# flex_led_wrap.net
KiCad netlist of a schematic drawn in EAGLE
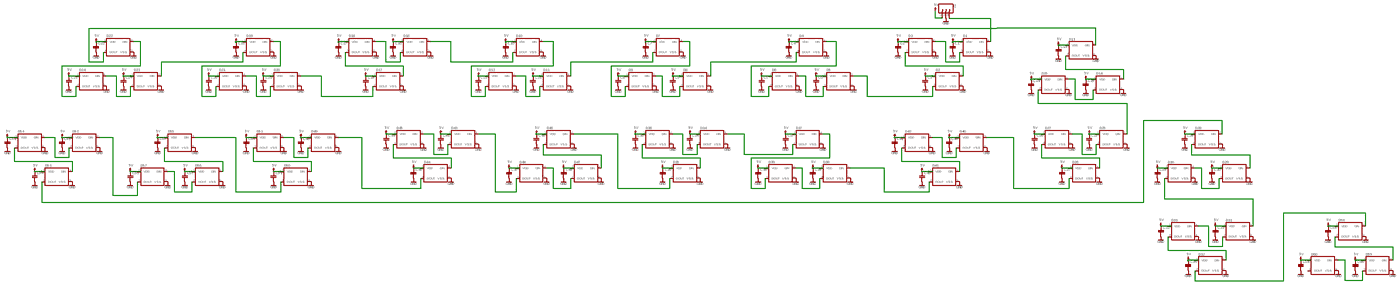
[diagram p0: schematic, sheet 1, overview]
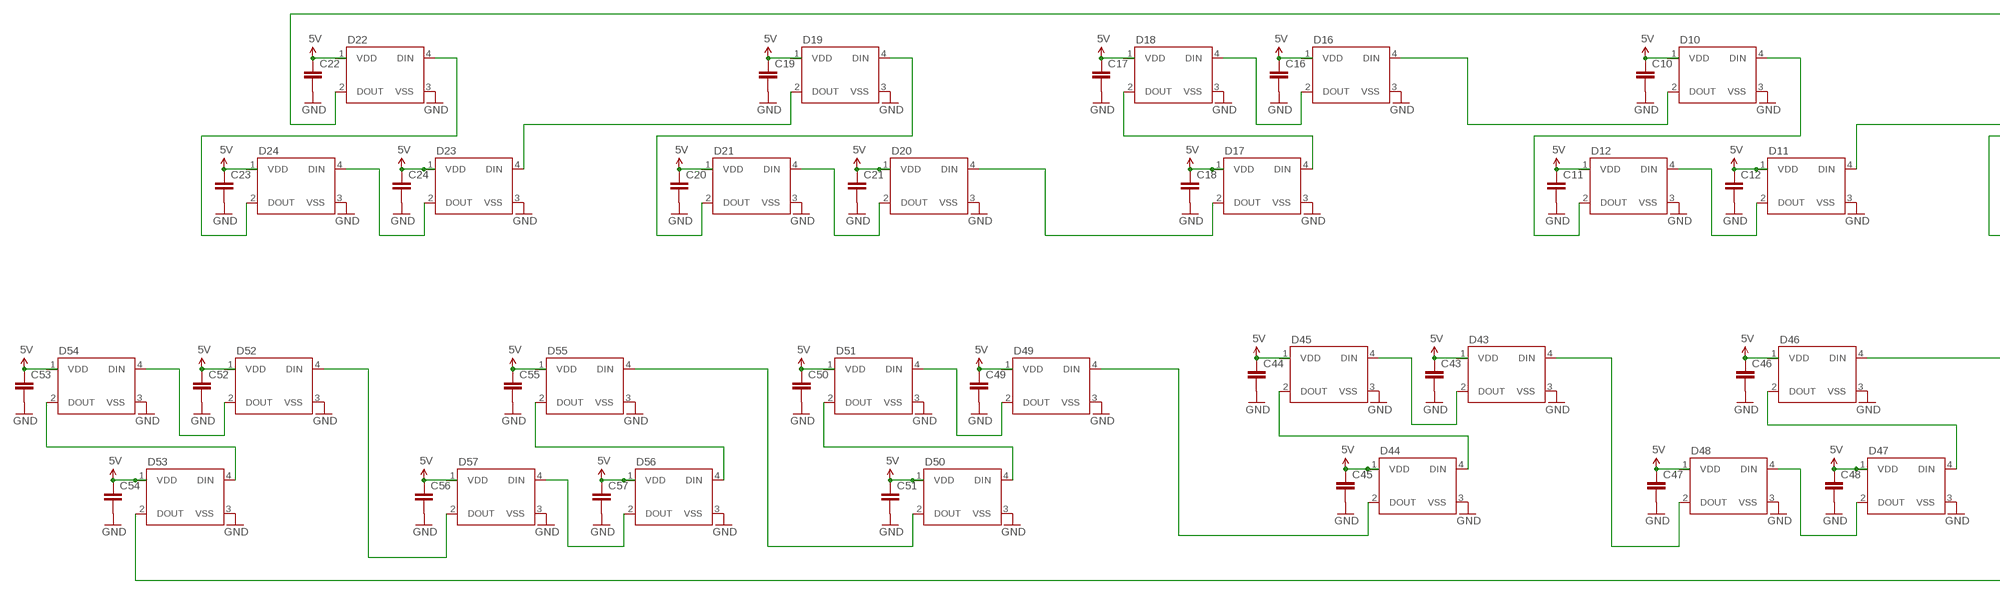
[diagram p1: schematic, sheet 1, part 1 of 4]
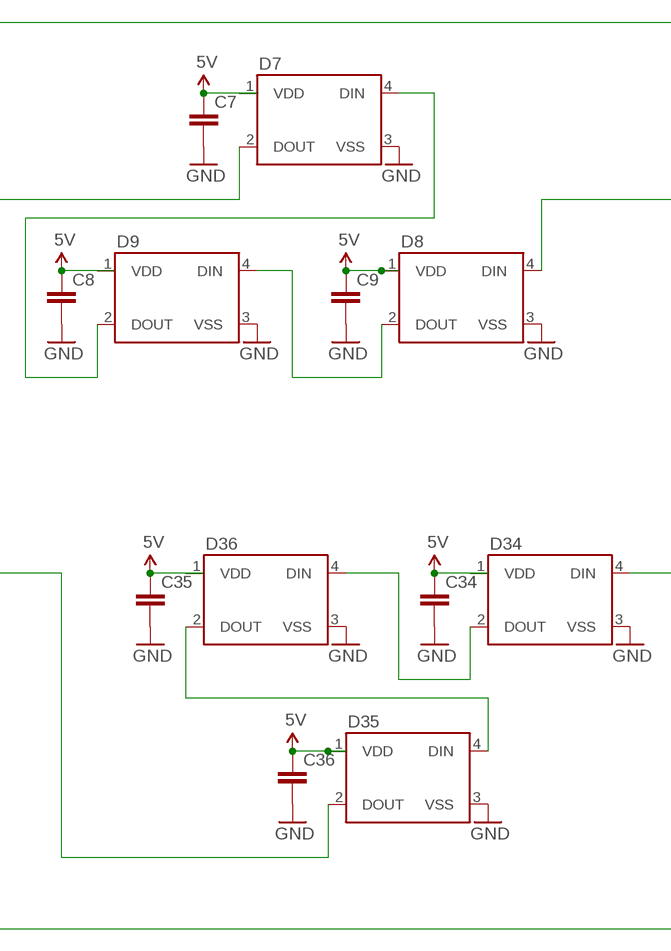
[diagram p2: schematic, sheet 1, part 2 of 4]
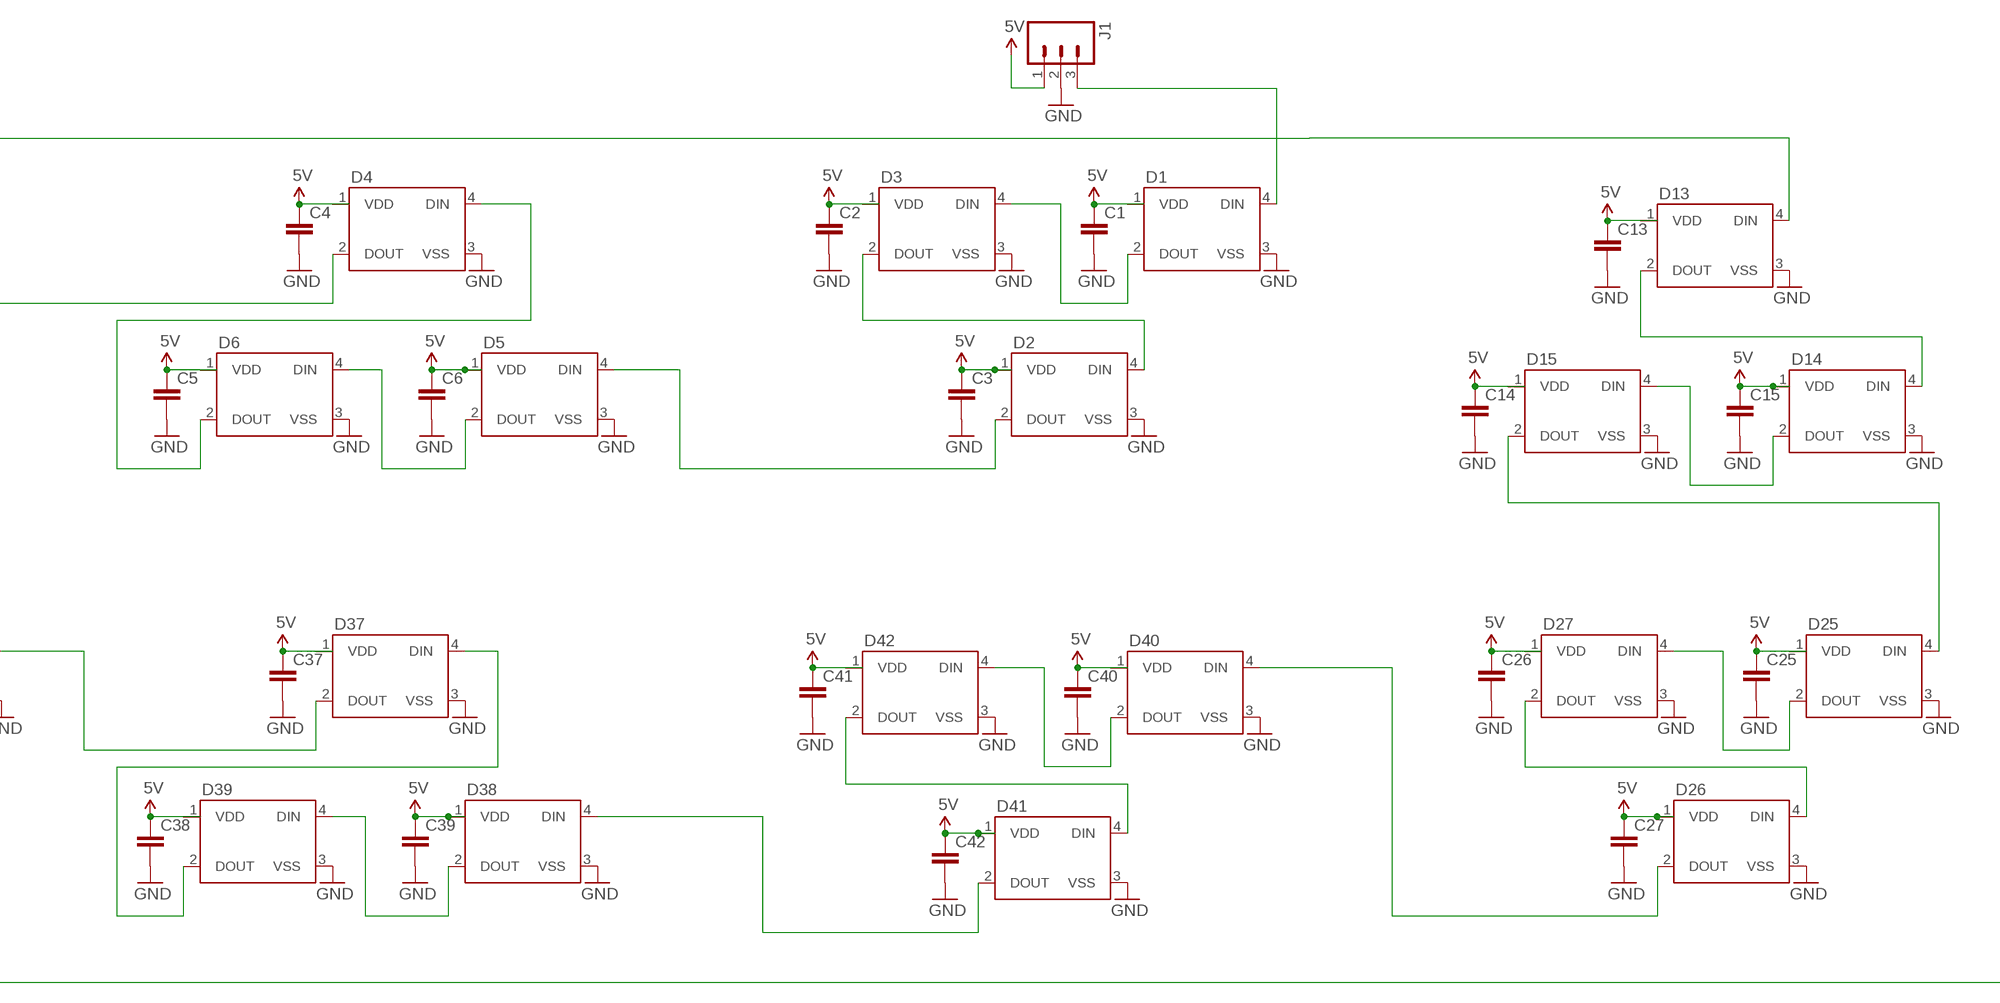
[diagram p3: schematic, sheet 1, part 3 of 4]
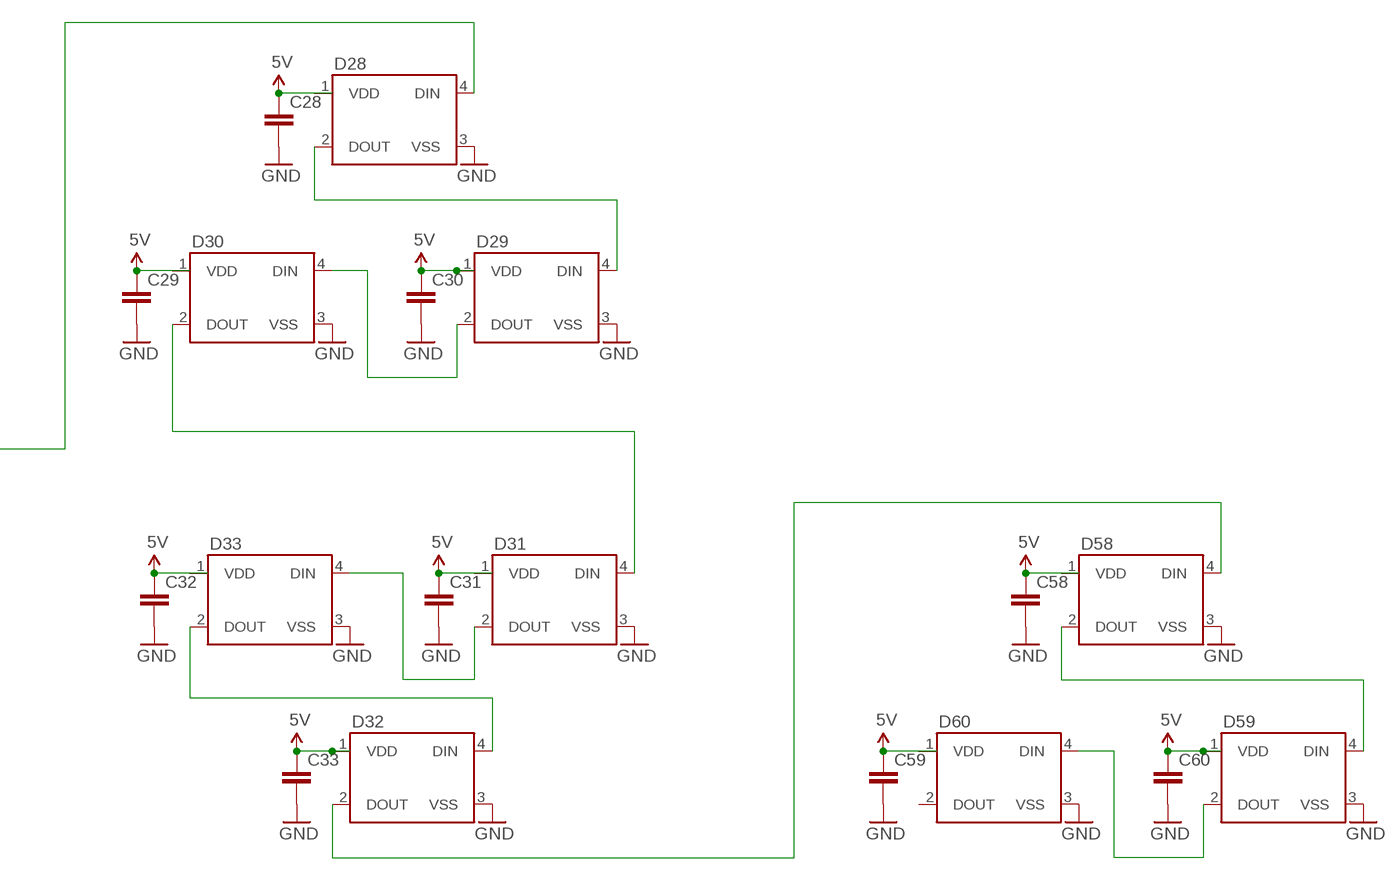
[diagram p4: schematic, sheet 1, part 4 of 4]

(export (version "E")
  (design (tool "Eeschema 10.0.6"))
  (components
    (comp (ref "C1")
      (value "CAP0805")
      (footprint "eagle-import:0805")
      (libsource (lib "eagle-import") (part "CAP0805"))
    )
    (comp (ref "C2")
      (value "CAP0805")
      (footprint "eagle-import:0805")
      (libsource (lib "eagle-import") (part "CAP0805"))
    )
    (comp (ref "C3")
      (value "CAP0805")
      (footprint "eagle-import:0805")
      (libsource (lib "eagle-import") (part "CAP0805"))
    )
    (comp (ref "C4")
      (value "CAP0805")
      (footprint "eagle-import:0805")
      (libsource (lib "eagle-import") (part "CAP0805"))
    )
    (comp (ref "C5")
      (value "CAP0805")
      (footprint "eagle-import:0805")
      (libsource (lib "eagle-import") (part "CAP0805"))
    )
    (comp (ref "C6")
      (value "CAP0805")
      (footprint "eagle-import:0805")
      (libsource (lib "eagle-import") (part "CAP0805"))
    )
    (comp (ref "C7")
      (value "CAP0805")
      (footprint "eagle-import:0805")
      (libsource (lib "eagle-import") (part "CAP0805"))
    )
    (comp (ref "C8")
      (value "CAP0805")
      (footprint "eagle-import:0805")
      (libsource (lib "eagle-import") (part "CAP0805"))
    )
    (comp (ref "C9")
      (value "CAP0805")
      (footprint "eagle-import:0805")
      (libsource (lib "eagle-import") (part "CAP0805"))
    )
    (comp (ref "C10")
      (value "CAP0805")
      (footprint "eagle-import:0805")
      (libsource (lib "eagle-import") (part "CAP0805"))
    )
    (comp (ref "C11")
      (value "CAP0805")
      (footprint "eagle-import:0805")
      (libsource (lib "eagle-import") (part "CAP0805"))
    )
    (comp (ref "C12")
      (value "CAP0805")
      (footprint "eagle-import:0805")
      (libsource (lib "eagle-import") (part "CAP0805"))
    )
    (comp (ref "C13")
      (value "CAP0805")
      (footprint "eagle-import:0805")
      (libsource (lib "eagle-import") (part "CAP0805"))
    )
    (comp (ref "C14")
      (value "CAP0805")
      (footprint "eagle-import:0805")
      (libsource (lib "eagle-import") (part "CAP0805"))
    )
    (comp (ref "C15")
      (value "CAP0805")
      (footprint "eagle-import:0805")
      (libsource (lib "eagle-import") (part "CAP0805"))
    )
    (comp (ref "C16")
      (value "CAP0805")
      (footprint "eagle-import:0805")
      (libsource (lib "eagle-import") (part "CAP0805"))
    )
    (comp (ref "C17")
      (value "CAP0805")
      (footprint "eagle-import:0805")
      (libsource (lib "eagle-import") (part "CAP0805"))
    )
    (comp (ref "C18")
      (value "CAP0805")
      (footprint "eagle-import:0805")
      (libsource (lib "eagle-import") (part "CAP0805"))
    )
    (comp (ref "C19")
      (value "CAP0805")
      (footprint "eagle-import:0805")
      (libsource (lib "eagle-import") (part "CAP0805"))
    )
    (comp (ref "C20")
      (value "CAP0805")
      (footprint "eagle-import:0805")
      (libsource (lib "eagle-import") (part "CAP0805"))
    )
    (comp (ref "C21")
      (value "CAP0805")
      (footprint "eagle-import:0805")
      (libsource (lib "eagle-import") (part "CAP0805"))
    )
    (comp (ref "C22")
      (value "CAP0805")
      (footprint "eagle-import:0805")
      (libsource (lib "eagle-import") (part "CAP0805"))
    )
    (comp (ref "C23")
      (value "CAP0805")
      (footprint "eagle-import:0805")
      (libsource (lib "eagle-import") (part "CAP0805"))
    )
    (comp (ref "C24")
      (value "CAP0805")
      (footprint "eagle-import:0805")
      (libsource (lib "eagle-import") (part "CAP0805"))
    )
    (comp (ref "C25")
      (value "CAP0805")
      (footprint "eagle-import:0805")
      (libsource (lib "eagle-import") (part "CAP0805"))
    )
    (comp (ref "C26")
      (value "CAP0805")
      (footprint "eagle-import:0805")
      (libsource (lib "eagle-import") (part "CAP0805"))
    )
    (comp (ref "C27")
      (value "CAP0805")
      (footprint "eagle-import:0805")
      (libsource (lib "eagle-import") (part "CAP0805"))
    )
    (comp (ref "C28")
      (value "CAP0805")
      (footprint "eagle-import:0805")
      (libsource (lib "eagle-import") (part "CAP0805"))
    )
    (comp (ref "C29")
      (value "CAP0805")
      (footprint "eagle-import:0805")
      (libsource (lib "eagle-import") (part "CAP0805"))
    )
    (comp (ref "C30")
      (value "CAP0805")
      (footprint "eagle-import:0805")
      (libsource (lib "eagle-import") (part "CAP0805"))
    )
    (comp (ref "C31")
      (value "CAP0805")
      (footprint "eagle-import:0805")
      (libsource (lib "eagle-import") (part "CAP0805"))
    )
    (comp (ref "C32")
      (value "CAP0805")
      (footprint "eagle-import:0805")
      (libsource (lib "eagle-import") (part "CAP0805"))
    )
    (comp (ref "C33")
      (value "CAP0805")
      (footprint "eagle-import:0805")
      (libsource (lib "eagle-import") (part "CAP0805"))
    )
    (comp (ref "C34")
      (value "CAP0805")
      (footprint "eagle-import:0805")
      (libsource (lib "eagle-import") (part "CAP0805"))
    )
    (comp (ref "C35")
      (value "CAP0805")
      (footprint "eagle-import:0805")
      (libsource (lib "eagle-import") (part "CAP0805"))
    )
    (comp (ref "C36")
      (value "CAP0805")
      (footprint "eagle-import:0805")
      (libsource (lib "eagle-import") (part "CAP0805"))
    )
    (comp (ref "C37")
      (value "CAP0805")
      (footprint "eagle-import:0805")
      (libsource (lib "eagle-import") (part "CAP0805"))
    )
    (comp (ref "C38")
      (value "CAP0805")
      (footprint "eagle-import:0805")
      (libsource (lib "eagle-import") (part "CAP0805"))
    )
    (comp (ref "C39")
      (value "CAP0805")
      (footprint "eagle-import:0805")
      (libsource (lib "eagle-import") (part "CAP0805"))
    )
    (comp (ref "C40")
      (value "CAP0805")
      (footprint "eagle-import:0805")
      (libsource (lib "eagle-import") (part "CAP0805"))
    )
    (comp (ref "C41")
      (value "CAP0805")
      (footprint "eagle-import:0805")
      (libsource (lib "eagle-import") (part "CAP0805"))
    )
    (comp (ref "C42")
      (value "CAP0805")
      (footprint "eagle-import:0805")
      (libsource (lib "eagle-import") (part "CAP0805"))
    )
    (comp (ref "C43")
      (value "CAP0805")
      (footprint "eagle-import:0805")
      (libsource (lib "eagle-import") (part "CAP0805"))
    )
    (comp (ref "C44")
      (value "CAP0805")
      (footprint "eagle-import:0805")
      (libsource (lib "eagle-import") (part "CAP0805"))
    )
    (comp (ref "C45")
      (value "CAP0805")
      (footprint "eagle-import:0805")
      (libsource (lib "eagle-import") (part "CAP0805"))
    )
    (comp (ref "C46")
      (value "CAP0805")
      (footprint "eagle-import:0805")
      (libsource (lib "eagle-import") (part "CAP0805"))
    )
    (comp (ref "C47")
      (value "CAP0805")
      (footprint "eagle-import:0805")
      (libsource (lib "eagle-import") (part "CAP0805"))
    )
    (comp (ref "C48")
      (value "CAP0805")
      (footprint "eagle-import:0805")
      (libsource (lib "eagle-import") (part "CAP0805"))
    )
    (comp (ref "C49")
      (value "CAP0805")
      (footprint "eagle-import:0805")
      (libsource (lib "eagle-import") (part "CAP0805"))
    )
    (comp (ref "C50")
      (value "CAP0805")
      (footprint "eagle-import:0805")
      (libsource (lib "eagle-import") (part "CAP0805"))
    )
    (comp (ref "C51")
      (value "CAP0805")
      (footprint "eagle-import:0805")
      (libsource (lib "eagle-import") (part "CAP0805"))
    )
    (comp (ref "C52")
      (value "CAP0805")
      (footprint "eagle-import:0805")
      (libsource (lib "eagle-import") (part "CAP0805"))
    )
    (comp (ref "C53")
      (value "CAP0805")
      (footprint "eagle-import:0805")
      (libsource (lib "eagle-import") (part "CAP0805"))
    )
    (comp (ref "C54")
      (value "CAP0805")
      (footprint "eagle-import:0805")
      (libsource (lib "eagle-import") (part "CAP0805"))
    )
    (comp (ref "C55")
      (value "CAP0805")
      (footprint "eagle-import:0805")
      (libsource (lib "eagle-import") (part "CAP0805"))
    )
    (comp (ref "C56")
      (value "CAP0805")
      (footprint "eagle-import:0805")
      (libsource (lib "eagle-import") (part "CAP0805"))
    )
    (comp (ref "C57")
      (value "CAP0805")
      (footprint "eagle-import:0805")
      (libsource (lib "eagle-import") (part "CAP0805"))
    )
    (comp (ref "C58")
      (value "CAP0805")
      (footprint "eagle-import:0805")
      (libsource (lib "eagle-import") (part "CAP0805"))
    )
    (comp (ref "C59")
      (value "CAP0805")
      (footprint "eagle-import:0805")
      (libsource (lib "eagle-import") (part "CAP0805"))
    )
    (comp (ref "C60")
      (value "CAP0805")
      (footprint "eagle-import:0805")
      (libsource (lib "eagle-import") (part "CAP0805"))
    )
    (comp (ref "D1")
      (value "WS2812B")
      (footprint "eagle-import:WS2812B")
      (libsource (lib "eagle-import") (part "WS2812B"))
    )
    (comp (ref "D2")
      (value "WS2812B")
      (footprint "eagle-import:WS2812B")
      (libsource (lib "eagle-import") (part "WS2812B"))
    )
    (comp (ref "D3")
      (value "WS2812B")
      (footprint "eagle-import:WS2812B")
      (libsource (lib "eagle-import") (part "WS2812B"))
    )
    (comp (ref "D4")
      (value "WS2812B")
      (footprint "eagle-import:WS2812B")
      (libsource (lib "eagle-import") (part "WS2812B"))
    )
    (comp (ref "D5")
      (value "WS2812B")
      (footprint "eagle-import:WS2812B")
      (libsource (lib "eagle-import") (part "WS2812B"))
    )
    (comp (ref "D6")
      (value "WS2812B")
      (footprint "eagle-import:WS2812B")
      (libsource (lib "eagle-import") (part "WS2812B"))
    )
    (comp (ref "D7")
      (value "WS2812B")
      (footprint "eagle-import:WS2812B")
      (libsource (lib "eagle-import") (part "WS2812B"))
    )
    (comp (ref "D8")
      (value "WS2812B")
      (footprint "eagle-import:WS2812B")
      (libsource (lib "eagle-import") (part "WS2812B"))
    )
    (comp (ref "D9")
      (value "WS2812B")
      (footprint "eagle-import:WS2812B")
      (libsource (lib "eagle-import") (part "WS2812B"))
    )
    (comp (ref "D10")
      (value "WS2812B")
      (footprint "eagle-import:WS2812B")
      (libsource (lib "eagle-import") (part "WS2812B"))
    )
    (comp (ref "D11")
      (value "WS2812B")
      (footprint "eagle-import:WS2812B")
      (libsource (lib "eagle-import") (part "WS2812B"))
    )
    (comp (ref "D12")
      (value "WS2812B")
      (footprint "eagle-import:WS2812B")
      (libsource (lib "eagle-import") (part "WS2812B"))
    )
    (comp (ref "D13")
      (value "WS2812B")
      (footprint "eagle-import:WS2812B")
      (libsource (lib "eagle-import") (part "WS2812B"))
    )
    (comp (ref "D14")
      (value "WS2812B")
      (footprint "eagle-import:WS2812B")
      (libsource (lib "eagle-import") (part "WS2812B"))
    )
    (comp (ref "D15")
      (value "WS2812B")
      (footprint "eagle-import:WS2812B")
      (libsource (lib "eagle-import") (part "WS2812B"))
    )
    (comp (ref "D16")
      (value "WS2812B")
      (footprint "eagle-import:WS2812B")
      (libsource (lib "eagle-import") (part "WS2812B"))
    )
    (comp (ref "D17")
      (value "WS2812B")
      (footprint "eagle-import:WS2812B")
      (libsource (lib "eagle-import") (part "WS2812B"))
    )
    (comp (ref "D18")
      (value "WS2812B")
      (footprint "eagle-import:WS2812B")
      (libsource (lib "eagle-import") (part "WS2812B"))
    )
    (comp (ref "D19")
      (value "WS2812B")
      (footprint "eagle-import:WS2812B")
      (libsource (lib "eagle-import") (part "WS2812B"))
    )
    (comp (ref "D20")
      (value "WS2812B")
      (footprint "eagle-import:WS2812B")
      (libsource (lib "eagle-import") (part "WS2812B"))
    )
    (comp (ref "D21")
      (value "WS2812B")
      (footprint "eagle-import:WS2812B")
      (libsource (lib "eagle-import") (part "WS2812B"))
    )
    (comp (ref "D22")
      (value "WS2812B")
      (footprint "eagle-import:WS2812B")
      (libsource (lib "eagle-import") (part "WS2812B"))
    )
    (comp (ref "D23")
      (value "WS2812B")
      (footprint "eagle-import:WS2812B")
      (libsource (lib "eagle-import") (part "WS2812B"))
    )
    (comp (ref "D24")
      (value "WS2812B")
      (footprint "eagle-import:WS2812B")
      (libsource (lib "eagle-import") (part "WS2812B"))
    )
    (comp (ref "D25")
      (value "WS2812B")
      (footprint "eagle-import:WS2812B")
      (libsource (lib "eagle-import") (part "WS2812B"))
    )
    (comp (ref "D26")
      (value "WS2812B")
      (footprint "eagle-import:WS2812B")
      (libsource (lib "eagle-import") (part "WS2812B"))
    )
    (comp (ref "D27")
      (value "WS2812B")
      (footprint "eagle-import:WS2812B")
      (libsource (lib "eagle-import") (part "WS2812B"))
    )
    (comp (ref "D28")
      (value "WS2812B")
      (footprint "eagle-import:WS2812B")
      (libsource (lib "eagle-import") (part "WS2812B"))
    )
    (comp (ref "D29")
      (value "WS2812B")
      (footprint "eagle-import:WS2812B")
      (libsource (lib "eagle-import") (part "WS2812B"))
    )
    (comp (ref "D30")
      (value "WS2812B")
      (footprint "eagle-import:WS2812B")
      (libsource (lib "eagle-import") (part "WS2812B"))
    )
    (comp (ref "D31")
      (value "WS2812B")
      (footprint "eagle-import:WS2812B")
      (libsource (lib "eagle-import") (part "WS2812B"))
    )
    (comp (ref "D32")
      (value "WS2812B")
      (footprint "eagle-import:WS2812B")
      (libsource (lib "eagle-import") (part "WS2812B"))
    )
    (comp (ref "D33")
      (value "WS2812B")
      (footprint "eagle-import:WS2812B")
      (libsource (lib "eagle-import") (part "WS2812B"))
    )
    (comp (ref "D34")
      (value "WS2812B")
      (footprint "eagle-import:WS2812B")
      (libsource (lib "eagle-import") (part "WS2812B"))
    )
    (comp (ref "D35")
      (value "WS2812B")
      (footprint "eagle-import:WS2812B")
      (libsource (lib "eagle-import") (part "WS2812B"))
    )
    (comp (ref "D36")
      (value "WS2812B")
      (footprint "eagle-import:WS2812B")
      (libsource (lib "eagle-import") (part "WS2812B"))
    )
    (comp (ref "D37")
      (value "WS2812B")
      (footprint "eagle-import:WS2812B")
      (libsource (lib "eagle-import") (part "WS2812B"))
    )
    (comp (ref "D38")
      (value "WS2812B")
      (footprint "eagle-import:WS2812B")
      (libsource (lib "eagle-import") (part "WS2812B"))
    )
    (comp (ref "D39")
      (value "WS2812B")
      (footprint "eagle-import:WS2812B")
      (libsource (lib "eagle-import") (part "WS2812B"))
    )
    (comp (ref "D40")
      (value "WS2812B")
      (footprint "eagle-import:WS2812B")
      (libsource (lib "eagle-import") (part "WS2812B"))
    )
    (comp (ref "D41")
      (value "WS2812B")
      (footprint "eagle-import:WS2812B")
      (libsource (lib "eagle-import") (part "WS2812B"))
    )
    (comp (ref "D42")
      (value "WS2812B")
      (footprint "eagle-import:WS2812B")
      (libsource (lib "eagle-import") (part "WS2812B"))
    )
    (comp (ref "D43")
      (value "WS2812B")
      (footprint "eagle-import:WS2812B")
      (libsource (lib "eagle-import") (part "WS2812B"))
    )
    (comp (ref "D44")
      (value "WS2812B")
      (footprint "eagle-import:WS2812B")
      (libsource (lib "eagle-import") (part "WS2812B"))
    )
    (comp (ref "D45")
      (value "WS2812B")
      (footprint "eagle-import:WS2812B")
      (libsource (lib "eagle-import") (part "WS2812B"))
    )
    (comp (ref "D46")
      (value "WS2812B")
      (footprint "eagle-import:WS2812B")
      (libsource (lib "eagle-import") (part "WS2812B"))
    )
    (comp (ref "D47")
      (value "WS2812B")
      (footprint "eagle-import:WS2812B")
      (libsource (lib "eagle-import") (part "WS2812B"))
    )
    (comp (ref "D48")
      (value "WS2812B")
      (footprint "eagle-import:WS2812B")
      (libsource (lib "eagle-import") (part "WS2812B"))
    )
    (comp (ref "D49")
      (value "WS2812B")
      (footprint "eagle-import:WS2812B")
      (libsource (lib "eagle-import") (part "WS2812B"))
    )
    (comp (ref "D50")
      (value "WS2812B")
      (footprint "eagle-import:WS2812B")
      (libsource (lib "eagle-import") (part "WS2812B"))
    )
    (comp (ref "D51")
      (value "WS2812B")
      (footprint "eagle-import:WS2812B")
      (libsource (lib "eagle-import") (part "WS2812B"))
    )
    (comp (ref "D52")
      (value "WS2812B")
      (footprint "eagle-import:WS2812B")
      (libsource (lib "eagle-import") (part "WS2812B"))
    )
    (comp (ref "D53")
      (value "WS2812B")
      (footprint "eagle-import:WS2812B")
      (libsource (lib "eagle-import") (part "WS2812B"))
    )
    (comp (ref "D54")
      (value "WS2812B")
      (footprint "eagle-import:WS2812B")
      (libsource (lib "eagle-import") (part "WS2812B"))
    )
    (comp (ref "D55")
      (value "WS2812B")
      (footprint "eagle-import:WS2812B")
      (libsource (lib "eagle-import") (part "WS2812B"))
    )
    (comp (ref "D56")
      (value "WS2812B")
      (footprint "eagle-import:WS2812B")
      (libsource (lib "eagle-import") (part "WS2812B"))
    )
    (comp (ref "D57")
      (value "WS2812B")
      (footprint "eagle-import:WS2812B")
      (libsource (lib "eagle-import") (part "WS2812B"))
    )
    (comp (ref "D58")
      (value "WS2812B")
      (footprint "eagle-import:WS2812B")
      (libsource (lib "eagle-import") (part "WS2812B"))
    )
    (comp (ref "D59")
      (value "WS2812B")
      (footprint "eagle-import:WS2812B")
      (libsource (lib "eagle-import") (part "WS2812B"))
    )
    (comp (ref "D60")
      (value "WS2812B")
      (footprint "eagle-import:WS2812B")
      (libsource (lib "eagle-import") (part "WS2812B"))
    )
    (comp (ref "J1")
      (value "M03LONGPADS")
      (footprint "eagle-import:1X03_LONGPADS")
      (libsource (lib "eagle-import") (part "M03LONGPADS"))
    )
  )
  (nets
    (net (code "1") (name "5V") (class "Default")
      (node (ref "C1") (pin "1") (pinfunction "1_1") (pintype "passive"))
      (node (ref "C10") (pin "1") (pinfunction "1_1") (pintype "passive"))
      (node (ref "C11") (pin "1") (pinfunction "1_1") (pintype "passive"))
      (node (ref "C12") (pin "1") (pinfunction "1_1") (pintype "passive"))
      (node (ref "C13") (pin "1") (pinfunction "1_1") (pintype "passive"))
      (node (ref "C14") (pin "1") (pinfunction "1_1") (pintype "passive"))
      (node (ref "C15") (pin "1") (pinfunction "1_1") (pintype "passive"))
      (node (ref "C16") (pin "1") (pinfunction "1_1") (pintype "passive"))
      (node (ref "C17") (pin "1") (pinfunction "1_1") (pintype "passive"))
      (node (ref "C18") (pin "1") (pinfunction "1_1") (pintype "passive"))
      (node (ref "C19") (pin "1") (pinfunction "1_1") (pintype "passive"))
      (node (ref "C2") (pin "1") (pinfunction "1_1") (pintype "passive"))
      (node (ref "C20") (pin "1") (pinfunction "1_1") (pintype "passive"))
      (node (ref "C21") (pin "1") (pinfunction "1_1") (pintype "passive"))
      (node (ref "C22") (pin "1") (pinfunction "1_1") (pintype "passive"))
      (node (ref "C23") (pin "1") (pinfunction "1_1") (pintype "passive"))
      (node (ref "C24") (pin "1") (pinfunction "1_1") (pintype "passive"))
      (node (ref "C25") (pin "1") (pinfunction "1_1") (pintype "passive"))
      (node (ref "C26") (pin "1") (pinfunction "1_1") (pintype "passive"))
      (node (ref "C27") (pin "1") (pinfunction "1_1") (pintype "passive"))
      (node (ref "C28") (pin "1") (pinfunction "1_1") (pintype "passive"))
      (node (ref "C29") (pin "1") (pinfunction "1_1") (pintype "passive"))
      (node (ref "C3") (pin "1") (pinfunction "1_1") (pintype "passive"))
      (node (ref "C30") (pin "1") (pinfunction "1_1") (pintype "passive"))
      (node (ref "C31") (pin "1") (pinfunction "1_1") (pintype "passive"))
      (node (ref "C32") (pin "1") (pinfunction "1_1") (pintype "passive"))
      (node (ref "C33") (pin "1") (pinfunction "1_1") (pintype "passive"))
      (node (ref "C34") (pin "1") (pinfunction "1_1") (pintype "passive"))
      (node (ref "C35") (pin "1") (pinfunction "1_1") (pintype "passive"))
      (node (ref "C36") (pin "1") (pinfunction "1_1") (pintype "passive"))
      (node (ref "C37") (pin "1") (pinfunction "1_1") (pintype "passive"))
      (node (ref "C38") (pin "1") (pinfunction "1_1") (pintype "passive"))
      (node (ref "C39") (pin "1") (pinfunction "1_1") (pintype "passive"))
      (node (ref "C4") (pin "1") (pinfunction "1_1") (pintype "passive"))
      (node (ref "C40") (pin "1") (pinfunction "1_1") (pintype "passive"))
      (node (ref "C41") (pin "1") (pinfunction "1_1") (pintype "passive"))
      (node (ref "C42") (pin "1") (pinfunction "1_1") (pintype "passive"))
      (node (ref "C43") (pin "1") (pinfunction "1_1") (pintype "passive"))
      (node (ref "C44") (pin "1") (pinfunction "1_1") (pintype "passive"))
      (node (ref "C45") (pin "1") (pinfunction "1_1") (pintype "passive"))
      (node (ref "C46") (pin "1") (pinfunction "1_1") (pintype "passive"))
      (node (ref "C47") (pin "1") (pinfunction "1_1") (pintype "passive"))
      (node (ref "C48") (pin "1") (pinfunction "1_1") (pintype "passive"))
      (node (ref "C49") (pin "1") (pinfunction "1_1") (pintype "passive"))
      (node (ref "C5") (pin "1") (pinfunction "1_1") (pintype "passive"))
      (node (ref "C50") (pin "1") (pinfunction "1_1") (pintype "passive"))
      (node (ref "C51") (pin "1") (pinfunction "1_1") (pintype "passive"))
      (node (ref "C52") (pin "1") (pinfunction "1_1") (pintype "passive"))
      (node (ref "C53") (pin "1") (pinfunction "1_1") (pintype "passive"))
      (node (ref "C54") (pin "1") (pinfunction "1_1") (pintype "passive"))
      (node (ref "C55") (pin "1") (pinfunction "1_1") (pintype "passive"))
      (node (ref "C56") (pin "1") (pinfunction "1_1") (pintype "passive"))
      (node (ref "C57") (pin "1") (pinfunction "1_1") (pintype "passive"))
      (node (ref "C58") (pin "1") (pinfunction "1_1") (pintype "passive"))
      (node (ref "C59") (pin "1") (pinfunction "1_1") (pintype "passive"))
      (node (ref "C6") (pin "1") (pinfunction "1_1") (pintype "passive"))
      (node (ref "C60") (pin "1") (pinfunction "1_1") (pintype "passive"))
      (node (ref "C7") (pin "1") (pinfunction "1_1") (pintype "passive"))
      (node (ref "C8") (pin "1") (pinfunction "1_1") (pintype "passive"))
      (node (ref "C9") (pin "1") (pinfunction "1_1") (pintype "passive"))
      (node (ref "D1") (pin "1") (pinfunction "VDD_1") (pintype "power_in"))
      (node (ref "D10") (pin "1") (pinfunction "VDD_1") (pintype "power_in"))
      (node (ref "D11") (pin "1") (pinfunction "VDD_1") (pintype "power_in"))
      (node (ref "D12") (pin "1") (pinfunction "VDD_1") (pintype "power_in"))
      (node (ref "D13") (pin "1") (pinfunction "VDD_1") (pintype "power_in"))
      (node (ref "D14") (pin "1") (pinfunction "VDD_1") (pintype "power_in"))
      (node (ref "D15") (pin "1") (pinfunction "VDD_1") (pintype "power_in"))
      (node (ref "D16") (pin "1") (pinfunction "VDD_1") (pintype "power_in"))
      (node (ref "D17") (pin "1") (pinfunction "VDD_1") (pintype "power_in"))
      (node (ref "D18") (pin "1") (pinfunction "VDD_1") (pintype "power_in"))
      (node (ref "D19") (pin "1") (pinfunction "VDD_1") (pintype "power_in"))
      (node (ref "D2") (pin "1") (pinfunction "VDD_1") (pintype "power_in"))
      (node (ref "D20") (pin "1") (pinfunction "VDD_1") (pintype "power_in"))
      (node (ref "D21") (pin "1") (pinfunction "VDD_1") (pintype "power_in"))
      (node (ref "D22") (pin "1") (pinfunction "VDD_1") (pintype "power_in"))
      (node (ref "D23") (pin "1") (pinfunction "VDD_1") (pintype "power_in"))
      (node (ref "D24") (pin "1") (pinfunction "VDD_1") (pintype "power_in"))
      (node (ref "D25") (pin "1") (pinfunction "VDD_1") (pintype "power_in"))
      (node (ref "D26") (pin "1") (pinfunction "VDD_1") (pintype "power_in"))
      (node (ref "D27") (pin "1") (pinfunction "VDD_1") (pintype "power_in"))
      (node (ref "D28") (pin "1") (pinfunction "VDD_1") (pintype "power_in"))
      (node (ref "D29") (pin "1") (pinfunction "VDD_1") (pintype "power_in"))
      (node (ref "D3") (pin "1") (pinfunction "VDD_1") (pintype "power_in"))
      (node (ref "D30") (pin "1") (pinfunction "VDD_1") (pintype "power_in"))
      (node (ref "D31") (pin "1") (pinfunction "VDD_1") (pintype "power_in"))
      (node (ref "D32") (pin "1") (pinfunction "VDD_1") (pintype "power_in"))
      (node (ref "D33") (pin "1") (pinfunction "VDD_1") (pintype "power_in"))
      (node (ref "D34") (pin "1") (pinfunction "VDD_1") (pintype "power_in"))
      (node (ref "D35") (pin "1") (pinfunction "VDD_1") (pintype "power_in"))
      (node (ref "D36") (pin "1") (pinfunction "VDD_1") (pintype "power_in"))
      (node (ref "D37") (pin "1") (pinfunction "VDD_1") (pintype "power_in"))
      (node (ref "D38") (pin "1") (pinfunction "VDD_1") (pintype "power_in"))
      (node (ref "D39") (pin "1") (pinfunction "VDD_1") (pintype "power_in"))
      (node (ref "D4") (pin "1") (pinfunction "VDD_1") (pintype "power_in"))
      (node (ref "D40") (pin "1") (pinfunction "VDD_1") (pintype "power_in"))
      (node (ref "D41") (pin "1") (pinfunction "VDD_1") (pintype "power_in"))
      (node (ref "D42") (pin "1") (pinfunction "VDD_1") (pintype "power_in"))
      (node (ref "D43") (pin "1") (pinfunction "VDD_1") (pintype "power_in"))
      (node (ref "D44") (pin "1") (pinfunction "VDD_1") (pintype "power_in"))
      (node (ref "D45") (pin "1") (pinfunction "VDD_1") (pintype "power_in"))
      (node (ref "D46") (pin "1") (pinfunction "VDD_1") (pintype "power_in"))
      (node (ref "D47") (pin "1") (pinfunction "VDD_1") (pintype "power_in"))
      (node (ref "D48") (pin "1") (pinfunction "VDD_1") (pintype "power_in"))
      (node (ref "D49") (pin "1") (pinfunction "VDD_1") (pintype "power_in"))
      (node (ref "D5") (pin "1") (pinfunction "VDD_1") (pintype "power_in"))
      (node (ref "D50") (pin "1") (pinfunction "VDD_1") (pintype "power_in"))
      (node (ref "D51") (pin "1") (pinfunction "VDD_1") (pintype "power_in"))
      (node (ref "D52") (pin "1") (pinfunction "VDD_1") (pintype "power_in"))
      (node (ref "D53") (pin "1") (pinfunction "VDD_1") (pintype "power_in"))
      (node (ref "D54") (pin "1") (pinfunction "VDD_1") (pintype "power_in"))
      (node (ref "D55") (pin "1") (pinfunction "VDD_1") (pintype "power_in"))
      (node (ref "D56") (pin "1") (pinfunction "VDD_1") (pintype "power_in"))
      (node (ref "D57") (pin "1") (pinfunction "VDD_1") (pintype "power_in"))
      (node (ref "D58") (pin "1") (pinfunction "VDD_1") (pintype "power_in"))
      (node (ref "D59") (pin "1") (pinfunction "VDD_1") (pintype "power_in"))
      (node (ref "D6") (pin "1") (pinfunction "VDD_1") (pintype "power_in"))
      (node (ref "D60") (pin "1") (pinfunction "VDD_1") (pintype "power_in"))
      (node (ref "D7") (pin "1") (pinfunction "VDD_1") (pintype "power_in"))
      (node (ref "D8") (pin "1") (pinfunction "VDD_1") (pintype "power_in"))
      (node (ref "D9") (pin "1") (pinfunction "VDD_1") (pintype "power_in"))
      (node (ref "J1") (pin "1") (pinfunction "1_1") (pintype "passive"))
    )
    (net (code "2") (name "GND") (class "Default")
      (node (ref "C1") (pin "2") (pinfunction "2_2") (pintype "passive"))
      (node (ref "C10") (pin "2") (pinfunction "2_2") (pintype "passive"))
      (node (ref "C11") (pin "2") (pinfunction "2_2") (pintype "passive"))
      (node (ref "C12") (pin "2") (pinfunction "2_2") (pintype "passive"))
      (node (ref "C13") (pin "2") (pinfunction "2_2") (pintype "passive"))
      (node (ref "C14") (pin "2") (pinfunction "2_2") (pintype "passive"))
      (node (ref "C15") (pin "2") (pinfunction "2_2") (pintype "passive"))
      (node (ref "C16") (pin "2") (pinfunction "2_2") (pintype "passive"))
      (node (ref "C17") (pin "2") (pinfunction "2_2") (pintype "passive"))
      (node (ref "C18") (pin "2") (pinfunction "2_2") (pintype "passive"))
      (node (ref "C19") (pin "2") (pinfunction "2_2") (pintype "passive"))
      (node (ref "C2") (pin "2") (pinfunction "2_2") (pintype "passive"))
      (node (ref "C20") (pin "2") (pinfunction "2_2") (pintype "passive"))
      (node (ref "C21") (pin "2") (pinfunction "2_2") (pintype "passive"))
      (node (ref "C22") (pin "2") (pinfunction "2_2") (pintype "passive"))
      (node (ref "C23") (pin "2") (pinfunction "2_2") (pintype "passive"))
      (node (ref "C24") (pin "2") (pinfunction "2_2") (pintype "passive"))
      (node (ref "C25") (pin "2") (pinfunction "2_2") (pintype "passive"))
      (node (ref "C26") (pin "2") (pinfunction "2_2") (pintype "passive"))
      (node (ref "C27") (pin "2") (pinfunction "2_2") (pintype "passive"))
      (node (ref "C28") (pin "2") (pinfunction "2_2") (pintype "passive"))
      (node (ref "C29") (pin "2") (pinfunction "2_2") (pintype "passive"))
      (node (ref "C3") (pin "2") (pinfunction "2_2") (pintype "passive"))
      (node (ref "C30") (pin "2") (pinfunction "2_2") (pintype "passive"))
      (node (ref "C31") (pin "2") (pinfunction "2_2") (pintype "passive"))
      (node (ref "C32") (pin "2") (pinfunction "2_2") (pintype "passive"))
      (node (ref "C33") (pin "2") (pinfunction "2_2") (pintype "passive"))
      (node (ref "C34") (pin "2") (pinfunction "2_2") (pintype "passive"))
      (node (ref "C35") (pin "2") (pinfunction "2_2") (pintype "passive"))
      (node (ref "C36") (pin "2") (pinfunction "2_2") (pintype "passive"))
      (node (ref "C37") (pin "2") (pinfunction "2_2") (pintype "passive"))
      (node (ref "C38") (pin "2") (pinfunction "2_2") (pintype "passive"))
      (node (ref "C39") (pin "2") (pinfunction "2_2") (pintype "passive"))
      (node (ref "C4") (pin "2") (pinfunction "2_2") (pintype "passive"))
      (node (ref "C40") (pin "2") (pinfunction "2_2") (pintype "passive"))
      (node (ref "C41") (pin "2") (pinfunction "2_2") (pintype "passive"))
      (node (ref "C42") (pin "2") (pinfunction "2_2") (pintype "passive"))
      (node (ref "C43") (pin "2") (pinfunction "2_2") (pintype "passive"))
      (node (ref "C44") (pin "2") (pinfunction "2_2") (pintype "passive"))
      (node (ref "C45") (pin "2") (pinfunction "2_2") (pintype "passive"))
      (node (ref "C46") (pin "2") (pinfunction "2_2") (pintype "passive"))
      (node (ref "C47") (pin "2") (pinfunction "2_2") (pintype "passive"))
      (node (ref "C48") (pin "2") (pinfunction "2_2") (pintype "passive"))
      (node (ref "C49") (pin "2") (pinfunction "2_2") (pintype "passive"))
      (node (ref "C5") (pin "2") (pinfunction "2_2") (pintype "passive"))
      (node (ref "C50") (pin "2") (pinfunction "2_2") (pintype "passive"))
      (node (ref "C51") (pin "2") (pinfunction "2_2") (pintype "passive"))
      (node (ref "C52") (pin "2") (pinfunction "2_2") (pintype "passive"))
      (node (ref "C53") (pin "2") (pinfunction "2_2") (pintype "passive"))
      (node (ref "C54") (pin "2") (pinfunction "2_2") (pintype "passive"))
      (node (ref "C55") (pin "2") (pinfunction "2_2") (pintype "passive"))
      (node (ref "C56") (pin "2") (pinfunction "2_2") (pintype "passive"))
      (node (ref "C57") (pin "2") (pinfunction "2_2") (pintype "passive"))
      (node (ref "C58") (pin "2") (pinfunction "2_2") (pintype "passive"))
      (node (ref "C59") (pin "2") (pinfunction "2_2") (pintype "passive"))
      (node (ref "C6") (pin "2") (pinfunction "2_2") (pintype "passive"))
      (node (ref "C60") (pin "2") (pinfunction "2_2") (pintype "passive"))
      (node (ref "C7") (pin "2") (pinfunction "2_2") (pintype "passive"))
      (node (ref "C8") (pin "2") (pinfunction "2_2") (pintype "passive"))
      (node (ref "C9") (pin "2") (pinfunction "2_2") (pintype "passive"))
      (node (ref "D1") (pin "3") (pinfunction "VSS_3") (pintype "power_in"))
      (node (ref "D10") (pin "3") (pinfunction "VSS_3") (pintype "power_in"))
      (node (ref "D11") (pin "3") (pinfunction "VSS_3") (pintype "power_in"))
      (node (ref "D12") (pin "3") (pinfunction "VSS_3") (pintype "power_in"))
      (node (ref "D13") (pin "3") (pinfunction "VSS_3") (pintype "power_in"))
      (node (ref "D14") (pin "3") (pinfunction "VSS_3") (pintype "power_in"))
      (node (ref "D15") (pin "3") (pinfunction "VSS_3") (pintype "power_in"))
      (node (ref "D16") (pin "3") (pinfunction "VSS_3") (pintype "power_in"))
      (node (ref "D17") (pin "3") (pinfunction "VSS_3") (pintype "power_in"))
      (node (ref "D18") (pin "3") (pinfunction "VSS_3") (pintype "power_in"))
      (node (ref "D19") (pin "3") (pinfunction "VSS_3") (pintype "power_in"))
      (node (ref "D2") (pin "3") (pinfunction "VSS_3") (pintype "power_in"))
      (node (ref "D20") (pin "3") (pinfunction "VSS_3") (pintype "power_in"))
      (node (ref "D21") (pin "3") (pinfunction "VSS_3") (pintype "power_in"))
      (node (ref "D22") (pin "3") (pinfunction "VSS_3") (pintype "power_in"))
      (node (ref "D23") (pin "3") (pinfunction "VSS_3") (pintype "power_in"))
      (node (ref "D24") (pin "3") (pinfunction "VSS_3") (pintype "power_in"))
      (node (ref "D25") (pin "3") (pinfunction "VSS_3") (pintype "power_in"))
      (node (ref "D26") (pin "3") (pinfunction "VSS_3") (pintype "power_in"))
      (node (ref "D27") (pin "3") (pinfunction "VSS_3") (pintype "power_in"))
      (node (ref "D28") (pin "3") (pinfunction "VSS_3") (pintype "power_in"))
      (node (ref "D29") (pin "3") (pinfunction "VSS_3") (pintype "power_in"))
      (node (ref "D3") (pin "3") (pinfunction "VSS_3") (pintype "power_in"))
      (node (ref "D30") (pin "3") (pinfunction "VSS_3") (pintype "power_in"))
      (node (ref "D31") (pin "3") (pinfunction "VSS_3") (pintype "power_in"))
      (node (ref "D32") (pin "3") (pinfunction "VSS_3") (pintype "power_in"))
      (node (ref "D33") (pin "3") (pinfunction "VSS_3") (pintype "power_in"))
      (node (ref "D34") (pin "3") (pinfunction "VSS_3") (pintype "power_in"))
      (node (ref "D35") (pin "3") (pinfunction "VSS_3") (pintype "power_in"))
      (node (ref "D36") (pin "3") (pinfunction "VSS_3") (pintype "power_in"))
      (node (ref "D37") (pin "3") (pinfunction "VSS_3") (pintype "power_in"))
      (node (ref "D38") (pin "3") (pinfunction "VSS_3") (pintype "power_in"))
      (node (ref "D39") (pin "3") (pinfunction "VSS_3") (pintype "power_in"))
      (node (ref "D4") (pin "3") (pinfunction "VSS_3") (pintype "power_in"))
      (node (ref "D40") (pin "3") (pinfunction "VSS_3") (pintype "power_in"))
      (node (ref "D41") (pin "3") (pinfunction "VSS_3") (pintype "power_in"))
      (node (ref "D42") (pin "3") (pinfunction "VSS_3") (pintype "power_in"))
      (node (ref "D43") (pin "3") (pinfunction "VSS_3") (pintype "power_in"))
      (node (ref "D44") (pin "3") (pinfunction "VSS_3") (pintype "power_in"))
      (node (ref "D45") (pin "3") (pinfunction "VSS_3") (pintype "power_in"))
      (node (ref "D46") (pin "3") (pinfunction "VSS_3") (pintype "power_in"))
      (node (ref "D47") (pin "3") (pinfunction "VSS_3") (pintype "power_in"))
      (node (ref "D48") (pin "3") (pinfunction "VSS_3") (pintype "power_in"))
      (node (ref "D49") (pin "3") (pinfunction "VSS_3") (pintype "power_in"))
      (node (ref "D5") (pin "3") (pinfunction "VSS_3") (pintype "power_in"))
      (node (ref "D50") (pin "3") (pinfunction "VSS_3") (pintype "power_in"))
      (node (ref "D51") (pin "3") (pinfunction "VSS_3") (pintype "power_in"))
      (node (ref "D52") (pin "3") (pinfunction "VSS_3") (pintype "power_in"))
      (node (ref "D53") (pin "3") (pinfunction "VSS_3") (pintype "power_in"))
      (node (ref "D54") (pin "3") (pinfunction "VSS_3") (pintype "power_in"))
      (node (ref "D55") (pin "3") (pinfunction "VSS_3") (pintype "power_in"))
      (node (ref "D56") (pin "3") (pinfunction "VSS_3") (pintype "power_in"))
      (node (ref "D57") (pin "3") (pinfunction "VSS_3") (pintype "power_in"))
      (node (ref "D58") (pin "3") (pinfunction "VSS_3") (pintype "power_in"))
      (node (ref "D59") (pin "3") (pinfunction "VSS_3") (pintype "power_in"))
      (node (ref "D6") (pin "3") (pinfunction "VSS_3") (pintype "power_in"))
      (node (ref "D60") (pin "3") (pinfunction "VSS_3") (pintype "power_in"))
      (node (ref "D7") (pin "3") (pinfunction "VSS_3") (pintype "power_in"))
      (node (ref "D8") (pin "3") (pinfunction "VSS_3") (pintype "power_in"))
      (node (ref "D9") (pin "3") (pinfunction "VSS_3") (pintype "power_in"))
      (node (ref "J1") (pin "2") (pinfunction "2_2") (pintype "passive"))
    )
    (net (code "3") (name "Net-(D1-DIN)") (class "Default")
      (node (ref "D1") (pin "4") (pinfunction "DIN_4") (pintype "input"))
      (node (ref "J1") (pin "3") (pinfunction "3_3") (pintype "passive"))
    )
    (net (code "4") (name "Net-(D1-DOUT)") (class "Default")
      (node (ref "D1") (pin "2") (pinfunction "DOUT_2") (pintype "output"))
      (node (ref "D3") (pin "4") (pinfunction "DIN_4") (pintype "input"))
    )
    (net (code "5") (name "Net-(D2-DIN)") (class "Default")
      (node (ref "D2") (pin "4") (pinfunction "DIN_4") (pintype "input"))
      (node (ref "D3") (pin "2") (pinfunction "DOUT_2") (pintype "output"))
    )
    (net (code "6") (name "Net-(D2-DOUT)") (class "Default")
      (node (ref "D2") (pin "2") (pinfunction "DOUT_2") (pintype "output"))
      (node (ref "D5") (pin "4") (pinfunction "DIN_4") (pintype "input"))
    )
    (net (code "7") (name "Net-(D4-DIN)") (class "Default")
      (node (ref "D4") (pin "4") (pinfunction "DIN_4") (pintype "input"))
      (node (ref "D6") (pin "2") (pinfunction "DOUT_2") (pintype "output"))
    )
    (net (code "8") (name "Net-(D4-DOUT)") (class "Default")
      (node (ref "D4") (pin "2") (pinfunction "DOUT_2") (pintype "output"))
      (node (ref "D8") (pin "4") (pinfunction "DIN_4") (pintype "input"))
    )
    (net (code "9") (name "Net-(D5-DOUT)") (class "Default")
      (node (ref "D5") (pin "2") (pinfunction "DOUT_2") (pintype "output"))
      (node (ref "D6") (pin "4") (pinfunction "DIN_4") (pintype "input"))
    )
    (net (code "10") (name "Net-(D7-DIN)") (class "Default")
      (node (ref "D7") (pin "4") (pinfunction "DIN_4") (pintype "input"))
      (node (ref "D9") (pin "2") (pinfunction "DOUT_2") (pintype "output"))
    )
    (net (code "11") (name "Net-(D8-DOUT)") (class "Default")
      (node (ref "D8") (pin "2") (pinfunction "DOUT_2") (pintype "output"))
      (node (ref "D9") (pin "4") (pinfunction "DIN_4") (pintype "input"))
    )
    (net (code "12") (name "Net-(D10-DIN)") (class "Default")
      (node (ref "D10") (pin "4") (pinfunction "DIN_4") (pintype "input"))
      (node (ref "D12") (pin "2") (pinfunction "DOUT_2") (pintype "output"))
    )
    (net (code "13") (name "Net-(D10-DOUT)") (class "Default")
      (node (ref "D10") (pin "2") (pinfunction "DOUT_2") (pintype "output"))
      (node (ref "D16") (pin "4") (pinfunction "DIN_4") (pintype "input"))
    )
    (net (code "14") (name "Net-(D11-DIN)") (class "Default")
      (node (ref "D11") (pin "4") (pinfunction "DIN_4") (pintype "input"))
      (node (ref "D7") (pin "2") (pinfunction "DOUT_2") (pintype "output"))
    )
    (net (code "15") (name "Net-(D11-DOUT)") (class "Default")
      (node (ref "D11") (pin "2") (pinfunction "DOUT_2") (pintype "output"))
      (node (ref "D12") (pin "4") (pinfunction "DIN_4") (pintype "input"))
    )
    (net (code "16") (name "Net-(D13-DIN)") (class "Default")
      (node (ref "D13") (pin "4") (pinfunction "DIN_4") (pintype "input"))
      (node (ref "D22") (pin "2") (pinfunction "DOUT_2") (pintype "output"))
    )
    (net (code "17") (name "Net-(D13-DOUT)") (class "Default")
      (node (ref "D13") (pin "2") (pinfunction "DOUT_2") (pintype "output"))
      (node (ref "D14") (pin "4") (pinfunction "DIN_4") (pintype "input"))
    )
    (net (code "18") (name "Net-(D14-DOUT)") (class "Default")
      (node (ref "D14") (pin "2") (pinfunction "DOUT_2") (pintype "output"))
      (node (ref "D15") (pin "4") (pinfunction "DIN_4") (pintype "input"))
    )
    (net (code "19") (name "Net-(D15-DOUT)") (class "Default")
      (node (ref "D15") (pin "2") (pinfunction "DOUT_2") (pintype "output"))
      (node (ref "D25") (pin "4") (pinfunction "DIN_4") (pintype "input"))
    )
    (net (code "20") (name "Net-(D16-DOUT)") (class "Default")
      (node (ref "D16") (pin "2") (pinfunction "DOUT_2") (pintype "output"))
      (node (ref "D18") (pin "4") (pinfunction "DIN_4") (pintype "input"))
    )
    (net (code "21") (name "Net-(D17-DIN)") (class "Default")
      (node (ref "D17") (pin "4") (pinfunction "DIN_4") (pintype "input"))
      (node (ref "D18") (pin "2") (pinfunction "DOUT_2") (pintype "output"))
    )
    (net (code "22") (name "Net-(D17-DOUT)") (class "Default")
      (node (ref "D17") (pin "2") (pinfunction "DOUT_2") (pintype "output"))
      (node (ref "D20") (pin "4") (pinfunction "DIN_4") (pintype "input"))
    )
    (net (code "23") (name "Net-(D19-DIN)") (class "Default")
      (node (ref "D19") (pin "4") (pinfunction "DIN_4") (pintype "input"))
      (node (ref "D21") (pin "2") (pinfunction "DOUT_2") (pintype "output"))
    )
    (net (code "24") (name "Net-(D19-DOUT)") (class "Default")
      (node (ref "D19") (pin "2") (pinfunction "DOUT_2") (pintype "output"))
      (node (ref "D23") (pin "4") (pinfunction "DIN_4") (pintype "input"))
    )
    (net (code "25") (name "Net-(D20-DOUT)") (class "Default")
      (node (ref "D20") (pin "2") (pinfunction "DOUT_2") (pintype "output"))
      (node (ref "D21") (pin "4") (pinfunction "DIN_4") (pintype "input"))
    )
    (net (code "26") (name "Net-(D22-DIN)") (class "Default")
      (node (ref "D22") (pin "4") (pinfunction "DIN_4") (pintype "input"))
      (node (ref "D24") (pin "2") (pinfunction "DOUT_2") (pintype "output"))
    )
    (net (code "27") (name "Net-(D23-DOUT)") (class "Default")
      (node (ref "D23") (pin "2") (pinfunction "DOUT_2") (pintype "output"))
      (node (ref "D24") (pin "4") (pinfunction "DIN_4") (pintype "input"))
    )
    (net (code "28") (name "Net-(D25-DOUT)") (class "Default")
      (node (ref "D25") (pin "2") (pinfunction "DOUT_2") (pintype "output"))
      (node (ref "D27") (pin "4") (pinfunction "DIN_4") (pintype "input"))
    )
    (net (code "29") (name "Net-(D26-DIN)") (class "Default")
      (node (ref "D26") (pin "4") (pinfunction "DIN_4") (pintype "input"))
      (node (ref "D27") (pin "2") (pinfunction "DOUT_2") (pintype "output"))
    )
    (net (code "30") (name "Net-(D26-DOUT)") (class "Default")
      (node (ref "D26") (pin "2") (pinfunction "DOUT_2") (pintype "output"))
      (node (ref "D40") (pin "4") (pinfunction "DIN_4") (pintype "input"))
    )
    (net (code "31") (name "Net-(D28-DIN)") (class "Default")
      (node (ref "D28") (pin "4") (pinfunction "DIN_4") (pintype "input"))
      (node (ref "D53") (pin "2") (pinfunction "DOUT_2") (pintype "output"))
    )
    (net (code "32") (name "Net-(D28-DOUT)") (class "Default")
      (node (ref "D28") (pin "2") (pinfunction "DOUT_2") (pintype "output"))
      (node (ref "D29") (pin "4") (pinfunction "DIN_4") (pintype "input"))
    )
    (net (code "33") (name "Net-(D29-DOUT)") (class "Default")
      (node (ref "D29") (pin "2") (pinfunction "DOUT_2") (pintype "output"))
      (node (ref "D30") (pin "4") (pinfunction "DIN_4") (pintype "input"))
    )
    (net (code "34") (name "Net-(D30-DOUT)") (class "Default")
      (node (ref "D30") (pin "2") (pinfunction "DOUT_2") (pintype "output"))
      (node (ref "D31") (pin "4") (pinfunction "DIN_4") (pintype "input"))
    )
    (net (code "35") (name "Net-(D31-DOUT)") (class "Default")
      (node (ref "D31") (pin "2") (pinfunction "DOUT_2") (pintype "output"))
      (node (ref "D33") (pin "4") (pinfunction "DIN_4") (pintype "input"))
    )
    (net (code "36") (name "Net-(D32-DIN)") (class "Default")
      (node (ref "D32") (pin "4") (pinfunction "DIN_4") (pintype "input"))
      (node (ref "D33") (pin "2") (pinfunction "DOUT_2") (pintype "output"))
    )
    (net (code "37") (name "Net-(D32-DOUT)") (class "Default")
      (node (ref "D32") (pin "2") (pinfunction "DOUT_2") (pintype "output"))
      (node (ref "D58") (pin "4") (pinfunction "DIN_4") (pintype "input"))
    )
    (net (code "38") (name "Net-(D34-DIN)") (class "Default")
      (node (ref "D34") (pin "4") (pinfunction "DIN_4") (pintype "input"))
      (node (ref "D37") (pin "2") (pinfunction "DOUT_2") (pintype "output"))
    )
    (net (code "39") (name "Net-(D34-DOUT)") (class "Default")
      (node (ref "D34") (pin "2") (pinfunction "DOUT_2") (pintype "output"))
      (node (ref "D36") (pin "4") (pinfunction "DIN_4") (pintype "input"))
    )
    (net (code "40") (name "Net-(D35-DIN)") (class "Default")
      (node (ref "D35") (pin "4") (pinfunction "DIN_4") (pintype "input"))
      (node (ref "D36") (pin "2") (pinfunction "DOUT_2") (pintype "output"))
    )
    (net (code "41") (name "Net-(D35-DOUT)") (class "Default")
      (node (ref "D35") (pin "2") (pinfunction "DOUT_2") (pintype "output"))
      (node (ref "D46") (pin "4") (pinfunction "DIN_4") (pintype "input"))
    )
    (net (code "42") (name "Net-(D37-DIN)") (class "Default")
      (node (ref "D37") (pin "4") (pinfunction "DIN_4") (pintype "input"))
      (node (ref "D39") (pin "2") (pinfunction "DOUT_2") (pintype "output"))
    )
    (net (code "43") (name "Net-(D38-DIN)") (class "Default")
      (node (ref "D38") (pin "4") (pinfunction "DIN_4") (pintype "input"))
      (node (ref "D41") (pin "2") (pinfunction "DOUT_2") (pintype "output"))
    )
    (net (code "44") (name "Net-(D38-DOUT)") (class "Default")
      (node (ref "D38") (pin "2") (pinfunction "DOUT_2") (pintype "output"))
      (node (ref "D39") (pin "4") (pinfunction "DIN_4") (pintype "input"))
    )
    (net (code "45") (name "Net-(D40-DOUT)") (class "Default")
      (node (ref "D40") (pin "2") (pinfunction "DOUT_2") (pintype "output"))
      (node (ref "D42") (pin "4") (pinfunction "DIN_4") (pintype "input"))
    )
    (net (code "46") (name "Net-(D41-DIN)") (class "Default")
      (node (ref "D41") (pin "4") (pinfunction "DIN_4") (pintype "input"))
      (node (ref "D42") (pin "2") (pinfunction "DOUT_2") (pintype "output"))
    )
    (net (code "47") (name "Net-(D43-DIN)") (class "Default")
      (node (ref "D43") (pin "4") (pinfunction "DIN_4") (pintype "input"))
      (node (ref "D48") (pin "2") (pinfunction "DOUT_2") (pintype "output"))
    )
    (net (code "48") (name "Net-(D43-DOUT)") (class "Default")
      (node (ref "D43") (pin "2") (pinfunction "DOUT_2") (pintype "output"))
      (node (ref "D45") (pin "4") (pinfunction "DIN_4") (pintype "input"))
    )
    (net (code "49") (name "Net-(D44-DIN)") (class "Default")
      (node (ref "D44") (pin "4") (pinfunction "DIN_4") (pintype "input"))
      (node (ref "D45") (pin "2") (pinfunction "DOUT_2") (pintype "output"))
    )
    (net (code "50") (name "Net-(D44-DOUT)") (class "Default")
      (node (ref "D44") (pin "2") (pinfunction "DOUT_2") (pintype "output"))
      (node (ref "D49") (pin "4") (pinfunction "DIN_4") (pintype "input"))
    )
    (net (code "51") (name "Net-(D46-DOUT)") (class "Default")
      (node (ref "D46") (pin "2") (pinfunction "DOUT_2") (pintype "output"))
      (node (ref "D47") (pin "4") (pinfunction "DIN_4") (pintype "input"))
    )
    (net (code "52") (name "Net-(D47-DOUT)") (class "Default")
      (node (ref "D47") (pin "2") (pinfunction "DOUT_2") (pintype "output"))
      (node (ref "D48") (pin "4") (pinfunction "DIN_4") (pintype "input"))
    )
    (net (code "53") (name "Net-(D49-DOUT)") (class "Default")
      (node (ref "D49") (pin "2") (pinfunction "DOUT_2") (pintype "output"))
      (node (ref "D51") (pin "4") (pinfunction "DIN_4") (pintype "input"))
    )
    (net (code "54") (name "Net-(D50-DIN)") (class "Default")
      (node (ref "D50") (pin "4") (pinfunction "DIN_4") (pintype "input"))
      (node (ref "D51") (pin "2") (pinfunction "DOUT_2") (pintype "output"))
    )
    (net (code "55") (name "Net-(D50-DOUT)") (class "Default")
      (node (ref "D50") (pin "2") (pinfunction "DOUT_2") (pintype "output"))
      (node (ref "D55") (pin "4") (pinfunction "DIN_4") (pintype "input"))
    )
    (net (code "56") (name "Net-(D52-DIN)") (class "Default")
      (node (ref "D52") (pin "4") (pinfunction "DIN_4") (pintype "input"))
      (node (ref "D57") (pin "2") (pinfunction "DOUT_2") (pintype "output"))
    )
    (net (code "57") (name "Net-(D52-DOUT)") (class "Default")
      (node (ref "D52") (pin "2") (pinfunction "DOUT_2") (pintype "output"))
      (node (ref "D54") (pin "4") (pinfunction "DIN_4") (pintype "input"))
    )
    (net (code "58") (name "Net-(D53-DIN)") (class "Default")
      (node (ref "D53") (pin "4") (pinfunction "DIN_4") (pintype "input"))
      (node (ref "D54") (pin "2") (pinfunction "DOUT_2") (pintype "output"))
    )
    (net (code "59") (name "Net-(D55-DOUT)") (class "Default")
      (node (ref "D55") (pin "2") (pinfunction "DOUT_2") (pintype "output"))
      (node (ref "D56") (pin "4") (pinfunction "DIN_4") (pintype "input"))
    )
    (net (code "60") (name "Net-(D56-DOUT)") (class "Default")
      (node (ref "D56") (pin "2") (pinfunction "DOUT_2") (pintype "output"))
      (node (ref "D57") (pin "4") (pinfunction "DIN_4") (pintype "input"))
    )
    (net (code "61") (name "Net-(D58-DOUT)") (class "Default")
      (node (ref "D58") (pin "2") (pinfunction "DOUT_2") (pintype "output"))
      (node (ref "D59") (pin "4") (pinfunction "DIN_4") (pintype "input"))
    )
    (net (code "62") (name "Net-(D59-DOUT)") (class "Default")
      (node (ref "D59") (pin "2") (pinfunction "DOUT_2") (pintype "output"))
      (node (ref "D60") (pin "4") (pinfunction "DIN_4") (pintype "input"))
    )
    (net (code "63") (name "unconnected-(D60-DOUT-Pad2)") (class "Default")
      (node (ref "D60") (pin "2") (pinfunction "DOUT_2") (pintype "output"))
    )
  )
)
